# MDL_RECEPTOR_IRF_1.net
KiCad netlist of a schematic drawn in Altium Designer
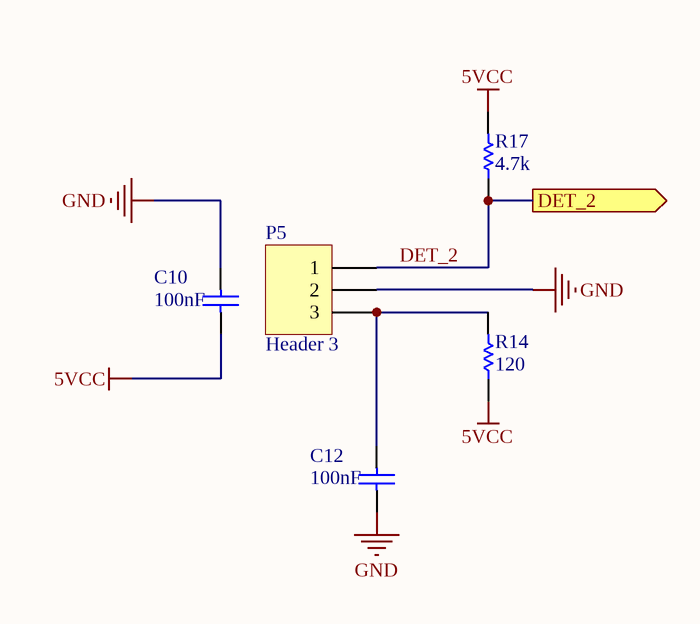
[diagram p0: MDL_RECEPTOR_IRF_1.SchDoc]

(export (version "E")
  (design (tool "Eeschema 10.0.6"))
  (components
    (comp (ref "C10")
      (value "100nF")
      (footprint "VP44-2.5")
      (description "Dipped Radial Multilayer Ceramic Capacitor X7R: 220nF, 100V")
      (fields (field (name "Comment") "VP44BY224JB") (field (name "PUBLISHER") "Altium Limited"))
      (libsource (lib "Vishay Vitramon Ceramic Dipped Capacitor") (part "VP44BY224JB"))
    )
    (comp (ref "C12")
      (value "100nF")
      (footprint "VP44-2.5")
      (description "Dipped Radial Multilayer Ceramic Capacitor X7R: 220nF, 100V")
      (fields (field (name "Comment") "VP44BY224JB") (field (name "PUBLISHER") "Altium Limited"))
      (libsource (lib "Vishay Vitramon Ceramic Dipped Capacitor") (part "VP44BY224JB"))
    )
    (comp (ref "P5")
      (value "Header 3")
      (footprint "HDR1X3")
      (description "Header, 3-Pin")
      (fields (field (name "PUBLISHER") "Altium Limited"))
      (libsource (lib "Miscellaneous Connectors") (part "Header 3"))
    )
    (comp (ref "R14")
      (value "120")
      (footprint "AXIAL-0.3")
      (description "Resistor")
      (fields (field (name "Comment") "Res") (field (name "PUBLISHER") "Altium Limited"))
      (libsource (lib "Miscellaneous Devices") (part "Res1"))
    )
    (comp (ref "R17")
      (value "4.7k")
      (footprint "AXIAL-0.3")
      (description "Resistor")
      (fields (field (name "Comment") "Res") (field (name "PUBLISHER") "Altium Limited"))
      (libsource (lib "Miscellaneous Devices") (part "Res1"))
    )
  )
  (nets
    (net (code "1") (name "/DET_2") (class "Default")
      (node (ref "P5") (pin "1") (pinfunction "1_1") (pintype "passive"))
      (node (ref "R17") (pin "1") (pinfunction "1_1") (pintype "passive"))
    )
    (net (code "2") (name "5VCC") (class "Default")
      (node (ref "C10") (pin "2") (pinfunction "2_2") (pintype "passive"))
      (node (ref "R14") (pin "1") (pinfunction "1_1") (pintype "passive"))
      (node (ref "R17") (pin "2") (pinfunction "2_2") (pintype "passive"))
    )
    (net (code "3") (name "GND") (class "Default")
      (node (ref "C10") (pin "1") (pinfunction "1_1") (pintype "passive"))
      (node (ref "C12") (pin "2") (pinfunction "2_2") (pintype "passive"))
      (node (ref "P5") (pin "2") (pinfunction "2_2") (pintype "passive"))
    )
    (net (code "4") (name "Net-(C12-Pad1)") (class "Default")
      (node (ref "C12") (pin "1") (pinfunction "1_1") (pintype "passive"))
      (node (ref "P5") (pin "3") (pinfunction "3_3") (pintype "passive"))
      (node (ref "R14") (pin "2") (pinfunction "2_2") (pintype "passive"))
    )
  )
)
